# main.net
KiCad netlist of a schematic drawn in EAGLE
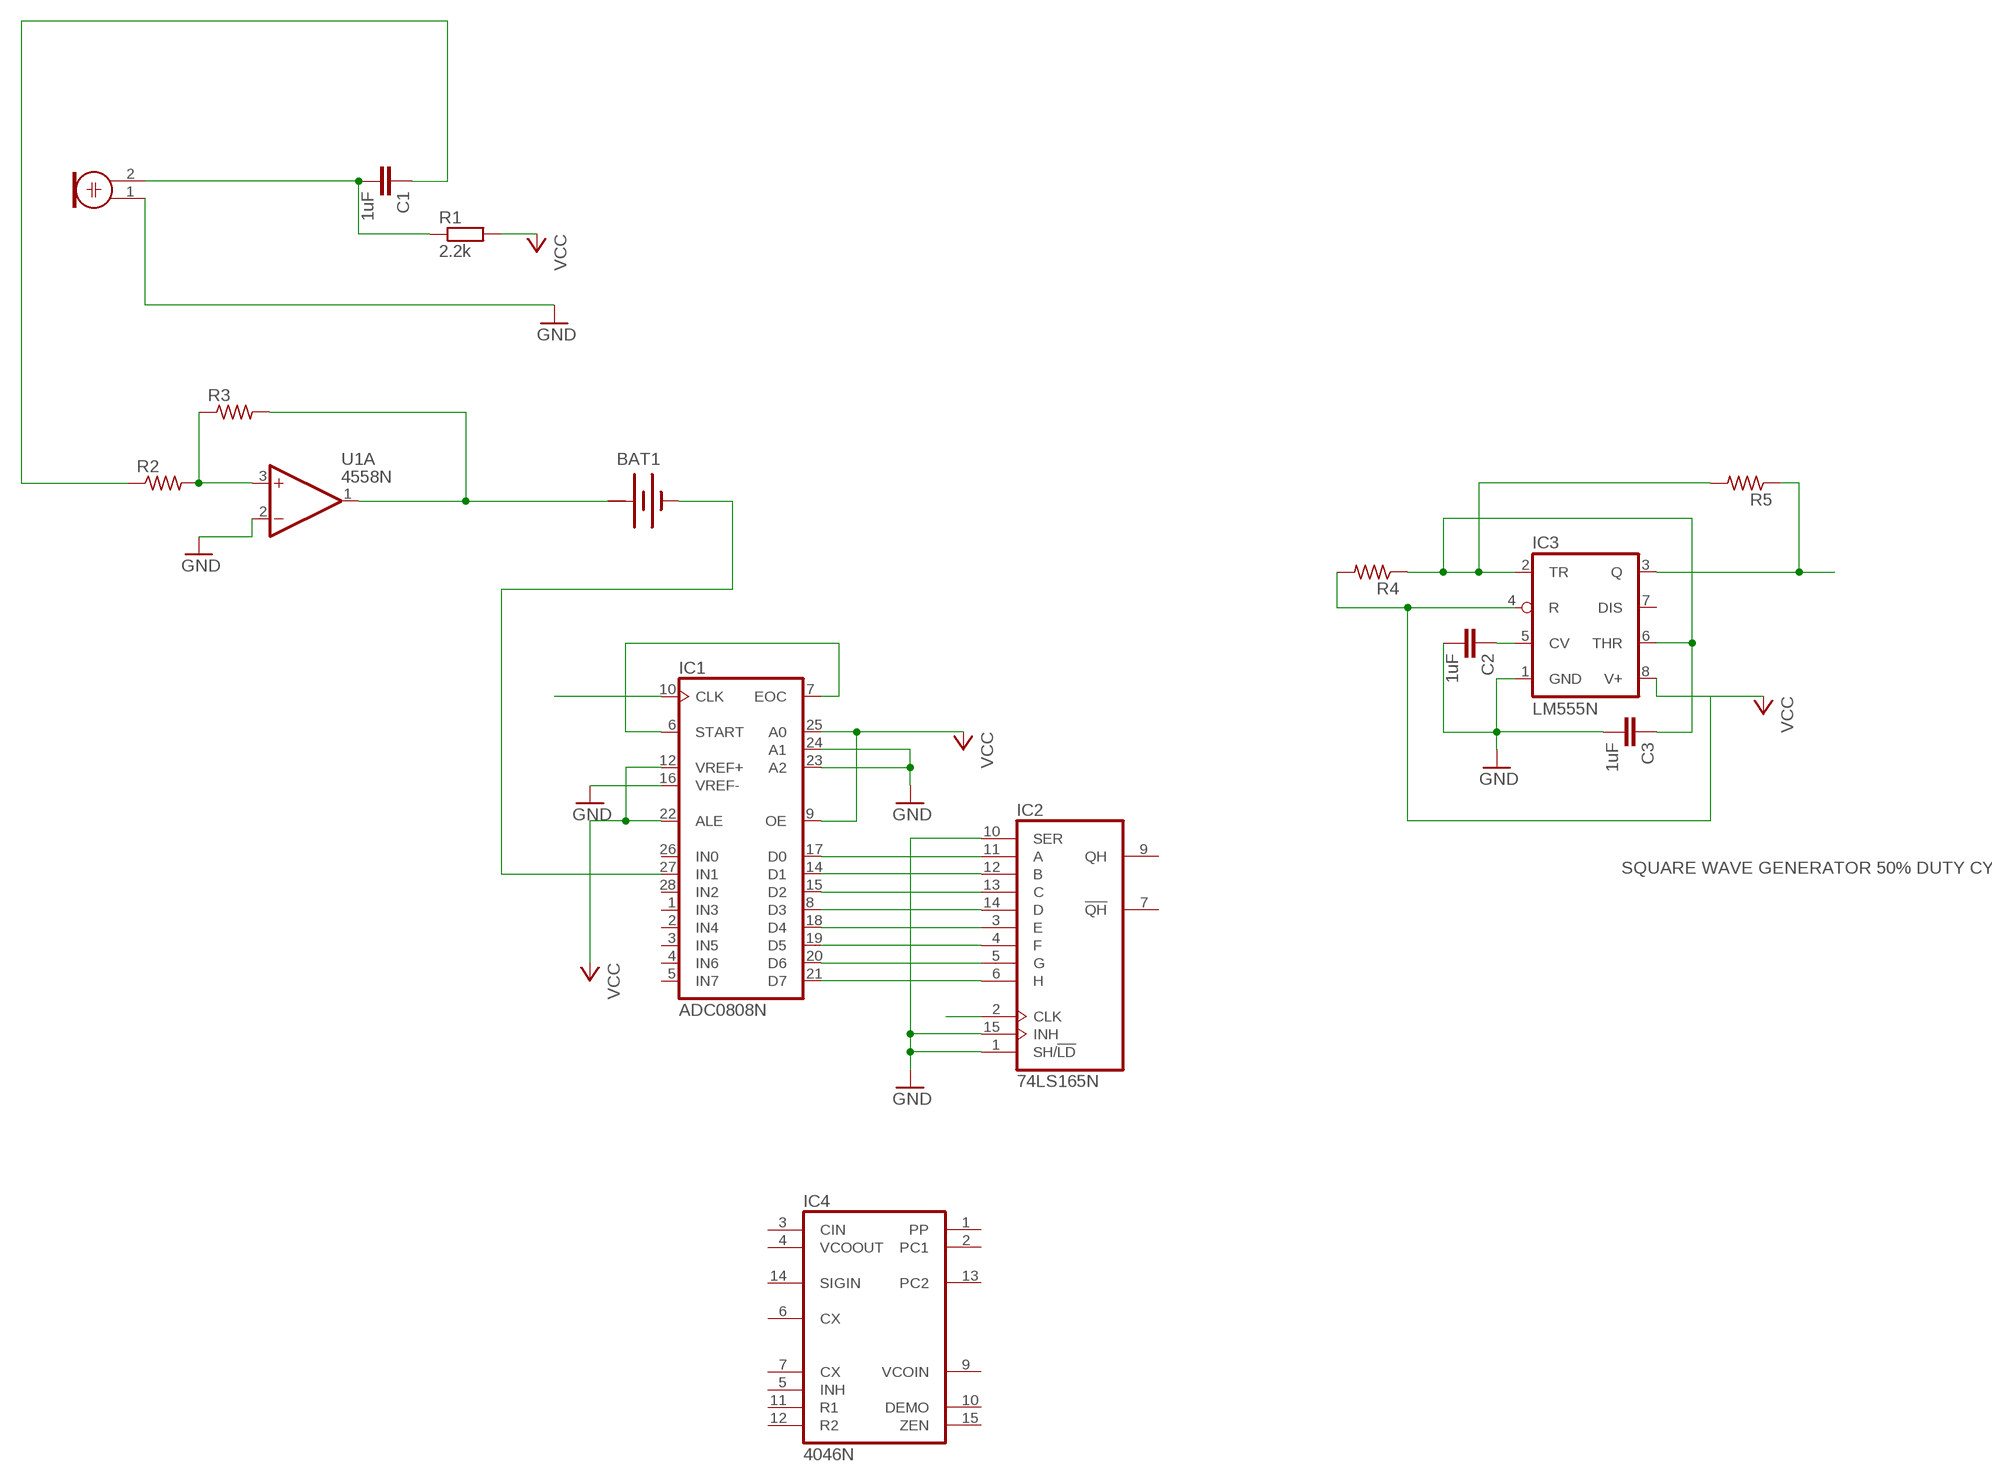
[diagram p0: schematic, sheet 1]

(export (version "E")
  (design (tool "Eeschema 10.0.6"))
  (components
    (comp (ref "BAT1")
      (value "BATTERY")
      (footprint "eagle-import:BATTERY")
      (libsource (lib "eagle-import") (part "BATTERY"))
    )
    (comp (ref "C1")
      (value "1uF")
      (footprint "eagle-import:C2.5-3")
      (libsource (lib "eagle-import") (part "C2,5-3"))
    )
    (comp (ref "C2")
      (value "1uF")
      (footprint "eagle-import:C2.5-3")
      (libsource (lib "eagle-import") (part "C2,5-3"))
    )
    (comp (ref "C3")
      (value "1uF")
      (footprint "eagle-import:C2.5-3")
      (libsource (lib "eagle-import") (part "C2,5-3"))
    )
    (comp (ref "IC1")
      (value "ADC0808N")
      (footprint "eagle-import:DIL28-6")
      (libsource (lib "eagle-import") (part "ADC0808N"))
    )
    (comp (ref "IC2")
      (value "74LS165N")
      (footprint "eagle-import:DIL16")
      (libsource (lib "eagle-import") (part "74165NLS"))
    )
    (comp (ref "IC3")
      (value "LM555N")
      (footprint "eagle-import:DIL08-ROUND")
      (libsource (lib "eagle-import") (part "555NLM"))
    )
    (comp (ref "IC4")
      (value "4046N")
      (footprint "eagle-import:DIL16")
      (libsource (lib "eagle-import") (part "4046N"))
    )
    (comp (ref "M1")
      (value "ELECTRET_MICROPHON-F6050AP")
      (footprint "eagle-import:F6050AP")
      (libsource (lib "eagle-import") (part "ELECTRET_MICROPHON-F6050AP"))
    )
    (comp (ref "R1")
      (value "2.2k")
      (footprint "eagle-import:0204_7")
      (libsource (lib "eagle-import") (part "R-EU_0204/7"))
    )
    (comp (ref "R2")
      (value "R-US_0204/7")
      (footprint "eagle-import:0204_7")
      (libsource (lib "eagle-import") (part "R-US_0204/7"))
    )
    (comp (ref "R3")
      (value "R-US_0204/7")
      (footprint "eagle-import:0204_7")
      (libsource (lib "eagle-import") (part "R-US_0204/7"))
    )
    (comp (ref "R4")
      (value "R-US_0204/7")
      (footprint "eagle-import:0204_7")
      (libsource (lib "eagle-import") (part "R-US_0204/7"))
    )
    (comp (ref "R5")
      (value "R-US_0204/7")
      (footprint "eagle-import:0204_7")
      (libsource (lib "eagle-import") (part "R-US_0204/7"))
    )
    (comp (ref "U1")
      (value "4558N")
      (footprint "eagle-import:DIL08")
      (libsource (lib "eagle-import") (part "4558N"))
    )
  )
  (nets
    (net (code "1") (name "+") (class "Default")
      (node (ref "BAT1") (pin "+@1") (pinfunction "+_+@1") (pintype "power_in"))
    )
    (net (code "2") (name "CLK") (class "Default")
      (node (ref "IC1") (pin "10") (pinfunction "CLK_10") (pintype "input"))
      (node (ref "IC2") (pin "2") (pinfunction "CLK_2") (pintype "input"))
      (node (ref "IC3") (pin "3") (pinfunction "Q_3") (pintype "output"))
      (node (ref "R5") (pin "1") (pinfunction "1_1") (pintype "passive"))
    )
    (net (code "3") (name "GND") (class "Default")
      (node (ref "C2") (pin "2") (pinfunction "2_2") (pintype "passive"))
      (node (ref "C3") (pin "2") (pinfunction "2_2") (pintype "passive"))
      (node (ref "IC1") (pin "16") (pinfunction "VREF-_16") (pintype "input"))
      (node (ref "IC1") (pin "23") (pinfunction "A2_23") (pintype "input"))
      (node (ref "IC1") (pin "24") (pinfunction "A1_24") (pintype "input"))
      (node (ref "IC2") (pin "1") (pinfunction "SH/~{LD}_1") (pintype "input"))
      (node (ref "IC2") (pin "10") (pinfunction "SER_10") (pintype "input"))
      (node (ref "IC2") (pin "15") (pinfunction "INH_15") (pintype "input"))
      (node (ref "IC3") (pin "1") (pinfunction "GND_1") (pintype "power_in"))
      (node (ref "M1") (pin "1") (pinfunction "1_1") (pintype "passive"))
      (node (ref "U1") (pin "2") (pinfunction "-IN_2") (pintype "input"))
    )
    (net (code "4") (name "Net-(C1-Pad1)") (class "Default")
      (node (ref "C1") (pin "1") (pinfunction "1_1") (pintype "passive"))
      (node (ref "R2") (pin "1") (pinfunction "1_1") (pintype "passive"))
    )
    (net (code "5") (name "Net-(C1-Pad2)") (class "Default")
      (node (ref "C1") (pin "2") (pinfunction "2_2") (pintype "passive"))
      (node (ref "M1") (pin "2") (pinfunction "2_2") (pintype "passive"))
      (node (ref "R1") (pin "1") (pinfunction "1_1") (pintype "passive"))
    )
    (net (code "6") (name "Net-(IC1A-D0)") (class "Default")
      (node (ref "IC1") (pin "17") (pinfunction "D0_17") (pintype "tri_state"))
      (node (ref "IC2") (pin "11") (pinfunction "A_11") (pintype "input"))
    )
    (net (code "7") (name "Net-(IC1A-D1)") (class "Default")
      (node (ref "IC1") (pin "14") (pinfunction "D1_14") (pintype "tri_state"))
      (node (ref "IC2") (pin "12") (pinfunction "B_12") (pintype "input"))
    )
    (net (code "8") (name "Net-(IC1A-D2)") (class "Default")
      (node (ref "IC1") (pin "15") (pinfunction "D2_15") (pintype "tri_state"))
      (node (ref "IC2") (pin "13") (pinfunction "C_13") (pintype "input"))
    )
    (net (code "9") (name "Net-(IC1A-D3)") (class "Default")
      (node (ref "IC1") (pin "8") (pinfunction "D3_8") (pintype "tri_state"))
      (node (ref "IC2") (pin "14") (pinfunction "D_14") (pintype "input"))
    )
    (net (code "10") (name "Net-(IC1A-D4)") (class "Default")
      (node (ref "IC1") (pin "18") (pinfunction "D4_18") (pintype "tri_state"))
      (node (ref "IC2") (pin "3") (pinfunction "E_3") (pintype "input"))
    )
    (net (code "11") (name "Net-(IC1A-D5)") (class "Default")
      (node (ref "IC1") (pin "19") (pinfunction "D5_19") (pintype "tri_state"))
      (node (ref "IC2") (pin "4") (pinfunction "F_4") (pintype "input"))
    )
    (net (code "12") (name "Net-(IC1A-D6)") (class "Default")
      (node (ref "IC1") (pin "20") (pinfunction "D6_20") (pintype "tri_state"))
      (node (ref "IC2") (pin "5") (pinfunction "G_5") (pintype "input"))
    )
    (net (code "13") (name "Net-(IC1A-D7)") (class "Default")
      (node (ref "IC1") (pin "21") (pinfunction "D7_21") (pintype "tri_state"))
      (node (ref "IC2") (pin "6") (pinfunction "H_6") (pintype "input"))
    )
    (net (code "14") (name "Net-(IC1A-EOC)") (class "Default")
      (node (ref "IC1") (pin "6") (pinfunction "START_6") (pintype "input"))
      (node (ref "IC1") (pin "7") (pinfunction "EOC_7") (pintype "output"))
    )
    (net (code "15") (name "Net-(IC1A-IN1)") (class "Default")
      (node (ref "BAT1") (pin "-") (pinfunction "-_-") (pintype "power_in"))
      (node (ref "IC1") (pin "27") (pinfunction "IN1_27") (pintype "input"))
    )
    (net (code "16") (name "Net-(IC3-CV)") (class "Default")
      (node (ref "C2") (pin "1") (pinfunction "1_1") (pintype "passive"))
      (node (ref "IC3") (pin "5") (pinfunction "CV_5") (pintype "input"))
    )
    (net (code "17") (name "Net-(IC3-THR)") (class "Default")
      (node (ref "C3") (pin "1") (pinfunction "1_1") (pintype "passive"))
      (node (ref "IC3") (pin "2") (pinfunction "TR_2") (pintype "input"))
      (node (ref "IC3") (pin "6") (pinfunction "THR_6") (pintype "input"))
      (node (ref "R4") (pin "1") (pinfunction "1_1") (pintype "passive"))
      (node (ref "R5") (pin "2") (pinfunction "2_2") (pintype "passive"))
    )
    (net (code "18") (name "Net-(U1A-+IN)") (class "Default")
      (node (ref "R2") (pin "2") (pinfunction "2_2") (pintype "passive"))
      (node (ref "R3") (pin "1") (pinfunction "1_1") (pintype "passive"))
      (node (ref "U1") (pin "3") (pinfunction "+IN_3") (pintype "input"))
    )
    (net (code "19") (name "Net-(U1A-OUT)") (class "Default")
      (node (ref "BAT1") (pin "+") (pinfunction "+_+") (pintype "power_in"))
      (node (ref "R3") (pin "2") (pinfunction "2_2") (pintype "passive"))
      (node (ref "U1") (pin "1") (pinfunction "OUT_1") (pintype "output"))
    )
    (net (code "20") (name "VCC") (class "Default")
      (node (ref "IC1") (pin "12") (pinfunction "VREF+_12") (pintype "input"))
      (node (ref "IC1") (pin "22") (pinfunction "ALE_22") (pintype "input"))
      (node (ref "IC1") (pin "25") (pinfunction "A0_25") (pintype "input"))
      (node (ref "IC1") (pin "9") (pinfunction "OE_9") (pintype "input"))
      (node (ref "IC3") (pin "4") (pinfunction "R_4") (pintype "input"))
      (node (ref "IC3") (pin "8") (pinfunction "V+_8") (pintype "power_in"))
      (node (ref "R1") (pin "2") (pinfunction "2_2") (pintype "passive"))
      (node (ref "R4") (pin "2") (pinfunction "2_2") (pintype "passive"))
    )
    (net (code "21") (name "unconnected-(IC1A-IN0-Pad26)") (class "Default")
      (node (ref "IC1") (pin "26") (pinfunction "IN0_26") (pintype "input"))
    )
    (net (code "22") (name "unconnected-(IC1A-IN2-Pad28)") (class "Default")
      (node (ref "IC1") (pin "28") (pinfunction "IN2_28") (pintype "input"))
    )
    (net (code "23") (name "unconnected-(IC1A-IN3-Pad1)") (class "Default")
      (node (ref "IC1") (pin "1") (pinfunction "IN3_1") (pintype "input"))
    )
    (net (code "24") (name "unconnected-(IC1A-IN4-Pad2)") (class "Default")
      (node (ref "IC1") (pin "2") (pinfunction "IN4_2") (pintype "input"))
    )
    (net (code "25") (name "unconnected-(IC1A-IN5-Pad3)") (class "Default")
      (node (ref "IC1") (pin "3") (pinfunction "IN5_3") (pintype "input"))
    )
    (net (code "26") (name "unconnected-(IC1A-IN6-Pad4)") (class "Default")
      (node (ref "IC1") (pin "4") (pinfunction "IN6_4") (pintype "input"))
    )
    (net (code "27") (name "unconnected-(IC1A-IN7-Pad5)") (class "Default")
      (node (ref "IC1") (pin "5") (pinfunction "IN7_5") (pintype "input"))
    )
    (net (code "28") (name "unconnected-(IC2A-QH-Pad9)") (class "Default")
      (node (ref "IC2") (pin "9") (pinfunction "QH_9") (pintype "output"))
    )
    (net (code "29") (name "unconnected-(IC2A-~{QH}-Pad7)") (class "Default")
      (node (ref "IC2") (pin "7") (pinfunction "~{QH}_7") (pintype "output"))
    )
    (net (code "30") (name "unconnected-(IC3-DIS-Pad7)") (class "Default")
      (node (ref "IC3") (pin "7") (pinfunction "DIS_7") (pintype "input"))
    )
    (net (code "31") (name "unconnected-(IC4A-CIN-Pad3)") (class "Default")
      (node (ref "IC4") (pin "3") (pinfunction "CIN_3") (pintype "input"))
    )
    (net (code "32") (name "unconnected-(IC4A-CX-Pad6)") (class "Default")
      (node (ref "IC4") (pin "6") (pinfunction "CX_6") (pintype "input"))
    )
    (net (code "33") (name "unconnected-(IC4A-CX-Pad7)") (class "Default")
      (node (ref "IC4") (pin "7") (pinfunction "CX_7") (pintype "input"))
    )
    (net (code "34") (name "unconnected-(IC4A-DEMO-Pad10)") (class "Default")
      (node (ref "IC4") (pin "10") (pinfunction "DEMO_10") (pintype "output"))
    )
    (net (code "35") (name "unconnected-(IC4A-INH-Pad5)") (class "Default")
      (node (ref "IC4") (pin "5") (pinfunction "INH_5") (pintype "input"))
    )
    (net (code "36") (name "unconnected-(IC4A-PC1-Pad2)") (class "Default")
      (node (ref "IC4") (pin "2") (pinfunction "PC1_2") (pintype "output"))
    )
    (net (code "37") (name "unconnected-(IC4A-PC2-Pad13)") (class "Default")
      (node (ref "IC4") (pin "13") (pinfunction "PC2_13") (pintype "output"))
    )
    (net (code "38") (name "unconnected-(IC4A-PP-Pad1)") (class "Default")
      (node (ref "IC4") (pin "1") (pinfunction "PP_1") (pintype "output"))
    )
    (net (code "39") (name "unconnected-(IC4A-R1-Pad11)") (class "Default")
      (node (ref "IC4") (pin "11") (pinfunction "R1_11") (pintype "input"))
    )
    (net (code "40") (name "unconnected-(IC4A-R2-Pad12)") (class "Default")
      (node (ref "IC4") (pin "12") (pinfunction "R2_12") (pintype "input"))
    )
    (net (code "41") (name "unconnected-(IC4A-SIGIN-Pad14)") (class "Default")
      (node (ref "IC4") (pin "14") (pinfunction "SIGIN_14") (pintype "input"))
    )
    (net (code "42") (name "unconnected-(IC4A-VCOIN-Pad9)") (class "Default")
      (node (ref "IC4") (pin "9") (pinfunction "VCOIN_9") (pintype "input"))
    )
    (net (code "43") (name "unconnected-(IC4A-VCOOUT-Pad4)") (class "Default")
      (node (ref "IC4") (pin "4") (pinfunction "VCOOUT_4") (pintype "output"))
    )
    (net (code "44") (name "unconnected-(IC4A-ZEN-Pad15)") (class "Default")
      (node (ref "IC4") (pin "15") (pinfunction "ZEN_15") (pintype "input"))
    )
  )
)
